# EPS_VBAT_EMI-Filter.net
KiCad netlist of a schematic drawn in Altium Designer
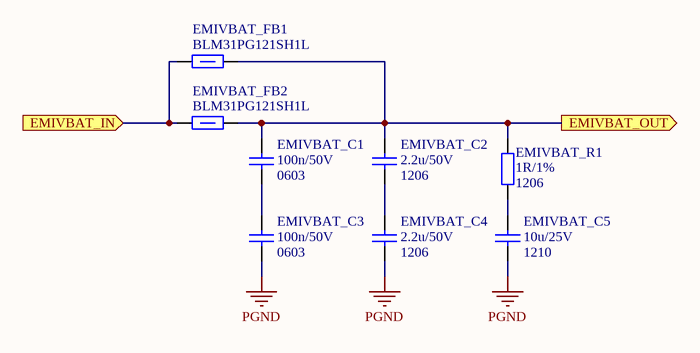
[diagram p0: EPS_VBAT_EMI-Filter.SchDoc]

(export (version "E")
  (design (tool "Eeschema 10.0.6"))
  (components
    (comp (ref "EMIVBAT_C1")
      (value "100n/50V")
      (footprint "SMD_Capacitor_0603")
      (description "Ceramic Cap Kemet COTS 100n/50V X7R 0603")
      (fields
        (field (name "MANUFACTURER") "Kemet")
        (field (name "MANUFACTURERPARTNUMBER") "C0603T104K5RALTU")
        (field (name "PACKAGE") "0603")
      )
      (libsource (lib "capacitors") (part "Cer_C0603T104K5RALTU"))
    )
    (comp (ref "EMIVBAT_C2")
      (value "2.2u/50V")
      (footprint "SMD_Capacitor_1206")
      (description "Ceramic Cap Murata Automotive 2.2u/50V X7R 1206")
      (fields
        (field (name "MANUFACTURER") "Murata")
        (field (name "MANUFACTURERPARTNUMBER") "GCJ31CR71H225KA12L")
        (field (name "PACKAGE") "1206")
      )
      (libsource (lib "capacitors") (part "Cer_GCJ31CR71H225KA12L"))
    )
    (comp (ref "EMIVBAT_C3")
      (value "100n/50V")
      (footprint "SMD_Capacitor_0603")
      (description "Ceramic Cap Kemet COTS 100n/50V X7R 0603")
      (fields
        (field (name "MANUFACTURER") "Kemet")
        (field (name "MANUFACTURERPARTNUMBER") "C0603T104K5RALTU")
        (field (name "PACKAGE") "0603")
      )
      (libsource (lib "capacitors") (part "Cer_C0603T104K5RALTU"))
    )
    (comp (ref "EMIVBAT_C4")
      (value "2.2u/50V")
      (footprint "SMD_Capacitor_1206")
      (description "Ceramic Cap Murata Automotive 2.2u/50V X7R 1206")
      (fields
        (field (name "MANUFACTURER") "Murata")
        (field (name "MANUFACTURERPARTNUMBER") "GCJ31CR71H225KA12L")
        (field (name "PACKAGE") "1206")
      )
      (libsource (lib "capacitors") (part "Cer_GCJ31CR71H225KA12L"))
    )
    (comp (ref "EMIVBAT_C5")
      (value "10u/25V")
      (footprint "SMD_Capacitor_1210")
      (description "Ceramic Cap Murata Automotive 10u/25V X7R 1210")
      (fields
        (field (name "MANUFACTURER") "Murata")
        (field (name "MANUFACTURERPARTNUMBER") "GCJ32ER71E106KA12L")
        (field (name "PACKAGE") "1210")
      )
      (libsource (lib "capacitors") (part "Cer_GCJ32ER71E106KA12L"))
    )
    (comp (ref "EMIVBAT_FB1")
      (value "120R/100MHz")
      (footprint "SMD_FerriteBead_1206")
      (description "Ferrite bead, 1206, 0.02HM, 3.5A.")
      (fields (field (name "MANUFACTURER") "Murata") (field (name "MANUFACTURERPARTNUMBER") "BLM31PG121SH1L"))
      (libsource (lib "inductors") (part "BLM31PG121SH1L"))
    )
    (comp (ref "EMIVBAT_FB2")
      (value "120R/100MHz")
      (footprint "SMD_FerriteBead_1206")
      (description "Ferrite bead, 1206, 0.02HM, 3.5A.")
      (fields (field (name "MANUFACTURER") "Murata") (field (name "MANUFACTURERPARTNUMBER") "BLM31PG121SH1L"))
      (libsource (lib "inductors") (part "BLM31PG121SH1L"))
    )
    (comp (ref "EMIVBAT_R1")
      (value "1R/1%")
      (footprint "SMD_Resistor_1206")
      (description "1R/1% Vishay CRCW 1206 Resistor. 250mW, 100ppm, 200V.")
      (fields
        (field (name "MANUFACTURERPARTNUMBER") "CRCW12061R00FKxxxx")
        (field (name "MANUFACTURER") "Vishay")
        (field (name "PACKAGE") "1206")
      )
      (libsource (lib "resistors") (part "CRCW12061R00FKxxxx"))
    )
  )
  (nets
    (net (code "1") (name "/EMIVBAT_IN") (class "Default")
      (node (ref "EMIVBAT_FB1") (pin "2") (pinfunction "2_2") (pintype "passive"))
      (node (ref "EMIVBAT_FB2") (pin "2") (pinfunction "2_2") (pintype "passive"))
    )
    (net (code "2") (name "/EMIVBAT_OUT") (class "Default")
      (node (ref "EMIVBAT_C1") (pin "1") (pinfunction "1_1") (pintype "passive"))
      (node (ref "EMIVBAT_C2") (pin "1") (pinfunction "1_1") (pintype "passive"))
      (node (ref "EMIVBAT_FB1") (pin "1") (pinfunction "1_1") (pintype "passive"))
      (node (ref "EMIVBAT_FB2") (pin "1") (pinfunction "1_1") (pintype "passive"))
      (node (ref "EMIVBAT_R1") (pin "1") (pinfunction "1_1") (pintype "passive"))
    )
    (net (code "3") (name "Net-(EMIVBAT_C1-Pad2)") (class "Default")
      (node (ref "EMIVBAT_C1") (pin "2") (pinfunction "2_2") (pintype "passive"))
      (node (ref "EMIVBAT_C3") (pin "1") (pinfunction "1_1") (pintype "passive"))
    )
    (net (code "4") (name "Net-(EMIVBAT_C2-Pad2)") (class "Default")
      (node (ref "EMIVBAT_C2") (pin "2") (pinfunction "2_2") (pintype "passive"))
      (node (ref "EMIVBAT_C4") (pin "1") (pinfunction "1_1") (pintype "passive"))
    )
    (net (code "5") (name "Net-(EMIVBAT_C5-Pad1)") (class "Default")
      (node (ref "EMIVBAT_C5") (pin "1") (pinfunction "1_1") (pintype "passive"))
      (node (ref "EMIVBAT_R1") (pin "2") (pinfunction "2_2") (pintype "passive"))
    )
    (net (code "6") (name "PGND") (class "Default")
      (node (ref "EMIVBAT_C3") (pin "2") (pinfunction "2_2") (pintype "passive"))
      (node (ref "EMIVBAT_C4") (pin "2") (pinfunction "2_2") (pintype "passive"))
      (node (ref "EMIVBAT_C5") (pin "2") (pinfunction "2_2") (pintype "passive"))
    )
  )
)
